# Rain_Gauge_PCB_V2.net
KiCad netlist of a schematic drawn in EAGLE
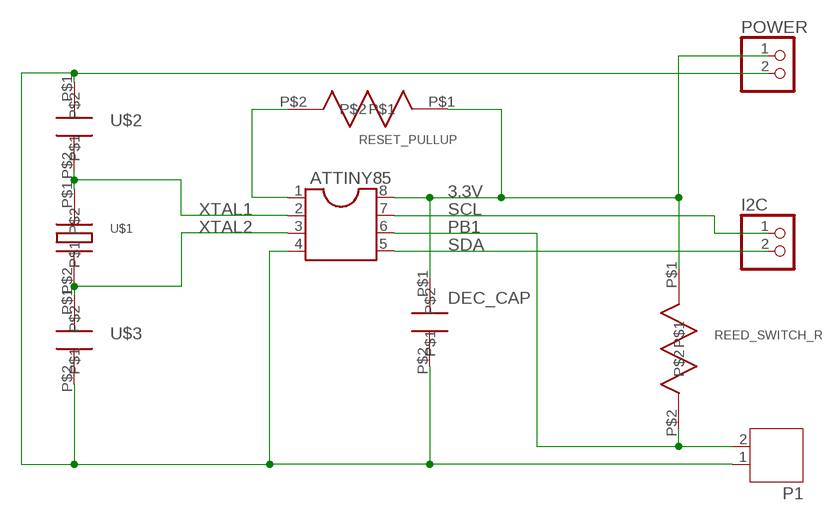
[diagram p0: schematic, sheet 1]

(export (version "E")
  (design (tool "Eeschema 10.0.6"))
  (components
    (comp (ref "ATTINY85")
      (value "DIL8")
      (footprint "eagle-import:DIL08")
      (libsource (lib "eagle-import") (part "DIL8"))
    )
    (comp (ref "DEC_CAP")
      (value "0603YC104KAZ2A")
      (footprint "eagle-import:0603YC104KAZ2A")
      (libsource (lib "eagle-import") (part "0603YC104KAZ2A"))
    )
    (comp (ref "I2C")
      (value "PINHD-1X2")
      (footprint "eagle-import:1X02")
      (libsource (lib "eagle-import") (part "PINHD-1X2"))
    )
    (comp (ref "P1")
      (value "JST-PH2")
      (footprint "eagle-import:JST-PH2")
      (libsource (lib "eagle-import") (part "JST-PH2"))
    )
    (comp (ref "POWER")
      (value "PINHD-1X2")
      (footprint "eagle-import:1X02")
      (libsource (lib "eagle-import") (part "PINHD-1X2"))
    )
    (comp (ref "REED_SWITCH_R")
      (value "RK73B2ATTD103J")
      (footprint "eagle-import:RK73B2ATTD103J")
      (libsource (lib "eagle-import") (part "RK73B2ATTD103J"))
    )
    (comp (ref "RESET_PULLUP")
      (value "RK73B2ATTD103J")
      (footprint "eagle-import:RK73B2ATTD103J")
      (libsource (lib "eagle-import") (part "RK73B2ATTD103J"))
    )
    (comp (ref "U$1")
      (value "QCL16.0000F18B23B")
      (footprint "eagle-import:QCL16.0000F18B23B")
      (libsource (lib "eagle-import") (part "QCL16.0000F18B23B"))
    )
    (comp (ref "U$2")
      (value "C0805C180J5GACTU")
      (footprint "eagle-import:C0805C180J5GACTU")
      (libsource (lib "eagle-import") (part "C0805C180J5GACTU"))
    )
    (comp (ref "U$3")
      (value "C0805C180J5GACTU")
      (footprint "eagle-import:C0805C180J5GACTU")
      (libsource (lib "eagle-import") (part "C0805C180J5GACTU"))
    )
  )
  (nets
    (net (code "1") (name "/3.3V") (class "Default")
      (node (ref "ATTINY85") (pin "8") (pinfunction "8_8") (pintype "passive"))
      (node (ref "DEC_CAP") (pin "P$1") (pinfunction "P$1_P$1") (pintype "bidirectional"))
      (node (ref "POWER") (pin "1") (pinfunction "1_1") (pintype "passive"))
      (node (ref "REED_SWITCH_R") (pin "P$1") (pinfunction "P$1_P$1") (pintype "bidirectional"))
      (node (ref "RESET_PULLUP") (pin "P$1") (pinfunction "P$1_P$1") (pintype "bidirectional"))
    )
    (net (code "2") (name "/PB1") (class "Default")
      (node (ref "ATTINY85") (pin "6") (pinfunction "6_6") (pintype "passive"))
      (node (ref "P1") (pin "2") (pinfunction "2_2") (pintype "passive"))
      (node (ref "REED_SWITCH_R") (pin "P$2") (pinfunction "P$2_P$2") (pintype "bidirectional"))
    )
    (net (code "3") (name "/SCL") (class "Default")
      (node (ref "ATTINY85") (pin "7") (pinfunction "7_7") (pintype "passive"))
      (node (ref "I2C") (pin "1") (pinfunction "1_1") (pintype "passive"))
    )
    (net (code "4") (name "/SDA") (class "Default")
      (node (ref "ATTINY85") (pin "5") (pinfunction "5_5") (pintype "passive"))
      (node (ref "I2C") (pin "2") (pinfunction "2_2") (pintype "passive"))
    )
    (net (code "5") (name "/XTAL1") (class "Default")
      (node (ref "ATTINY85") (pin "2") (pinfunction "2_2") (pintype "passive"))
      (node (ref "U$1") (pin "P$1") (pinfunction "P$1_P$1") (pintype "bidirectional"))
      (node (ref "U$2") (pin "P$2") (pinfunction "P$2_P$2") (pintype "bidirectional"))
    )
    (net (code "6") (name "/XTAL2") (class "Default")
      (node (ref "ATTINY85") (pin "3") (pinfunction "3_3") (pintype "passive"))
      (node (ref "U$1") (pin "P$2") (pinfunction "P$2_P$2") (pintype "bidirectional"))
      (node (ref "U$3") (pin "P$1") (pinfunction "P$1_P$1") (pintype "bidirectional"))
    )
    (net (code "7") (name "Net-(ATTINY85-Pad1)") (class "Default")
      (node (ref "ATTINY85") (pin "1") (pinfunction "1_1") (pintype "passive"))
      (node (ref "RESET_PULLUP") (pin "P$2") (pinfunction "P$2_P$2") (pintype "bidirectional"))
    )
    (net (code "8") (name "Net-(ATTINY85-Pad4)") (class "Default")
      (node (ref "ATTINY85") (pin "4") (pinfunction "4_4") (pintype "passive"))
      (node (ref "DEC_CAP") (pin "P$2") (pinfunction "P$2_P$2") (pintype "bidirectional"))
      (node (ref "P1") (pin "1") (pinfunction "1_1") (pintype "passive"))
      (node (ref "POWER") (pin "2") (pinfunction "2_2") (pintype "passive"))
      (node (ref "U$2") (pin "P$1") (pinfunction "P$1_P$1") (pintype "bidirectional"))
      (node (ref "U$3") (pin "P$2") (pinfunction "P$2_P$2") (pintype "bidirectional"))
    )
  )
)
